# P08R7.net
KiCad netlist of a schematic drawn in EAGLE
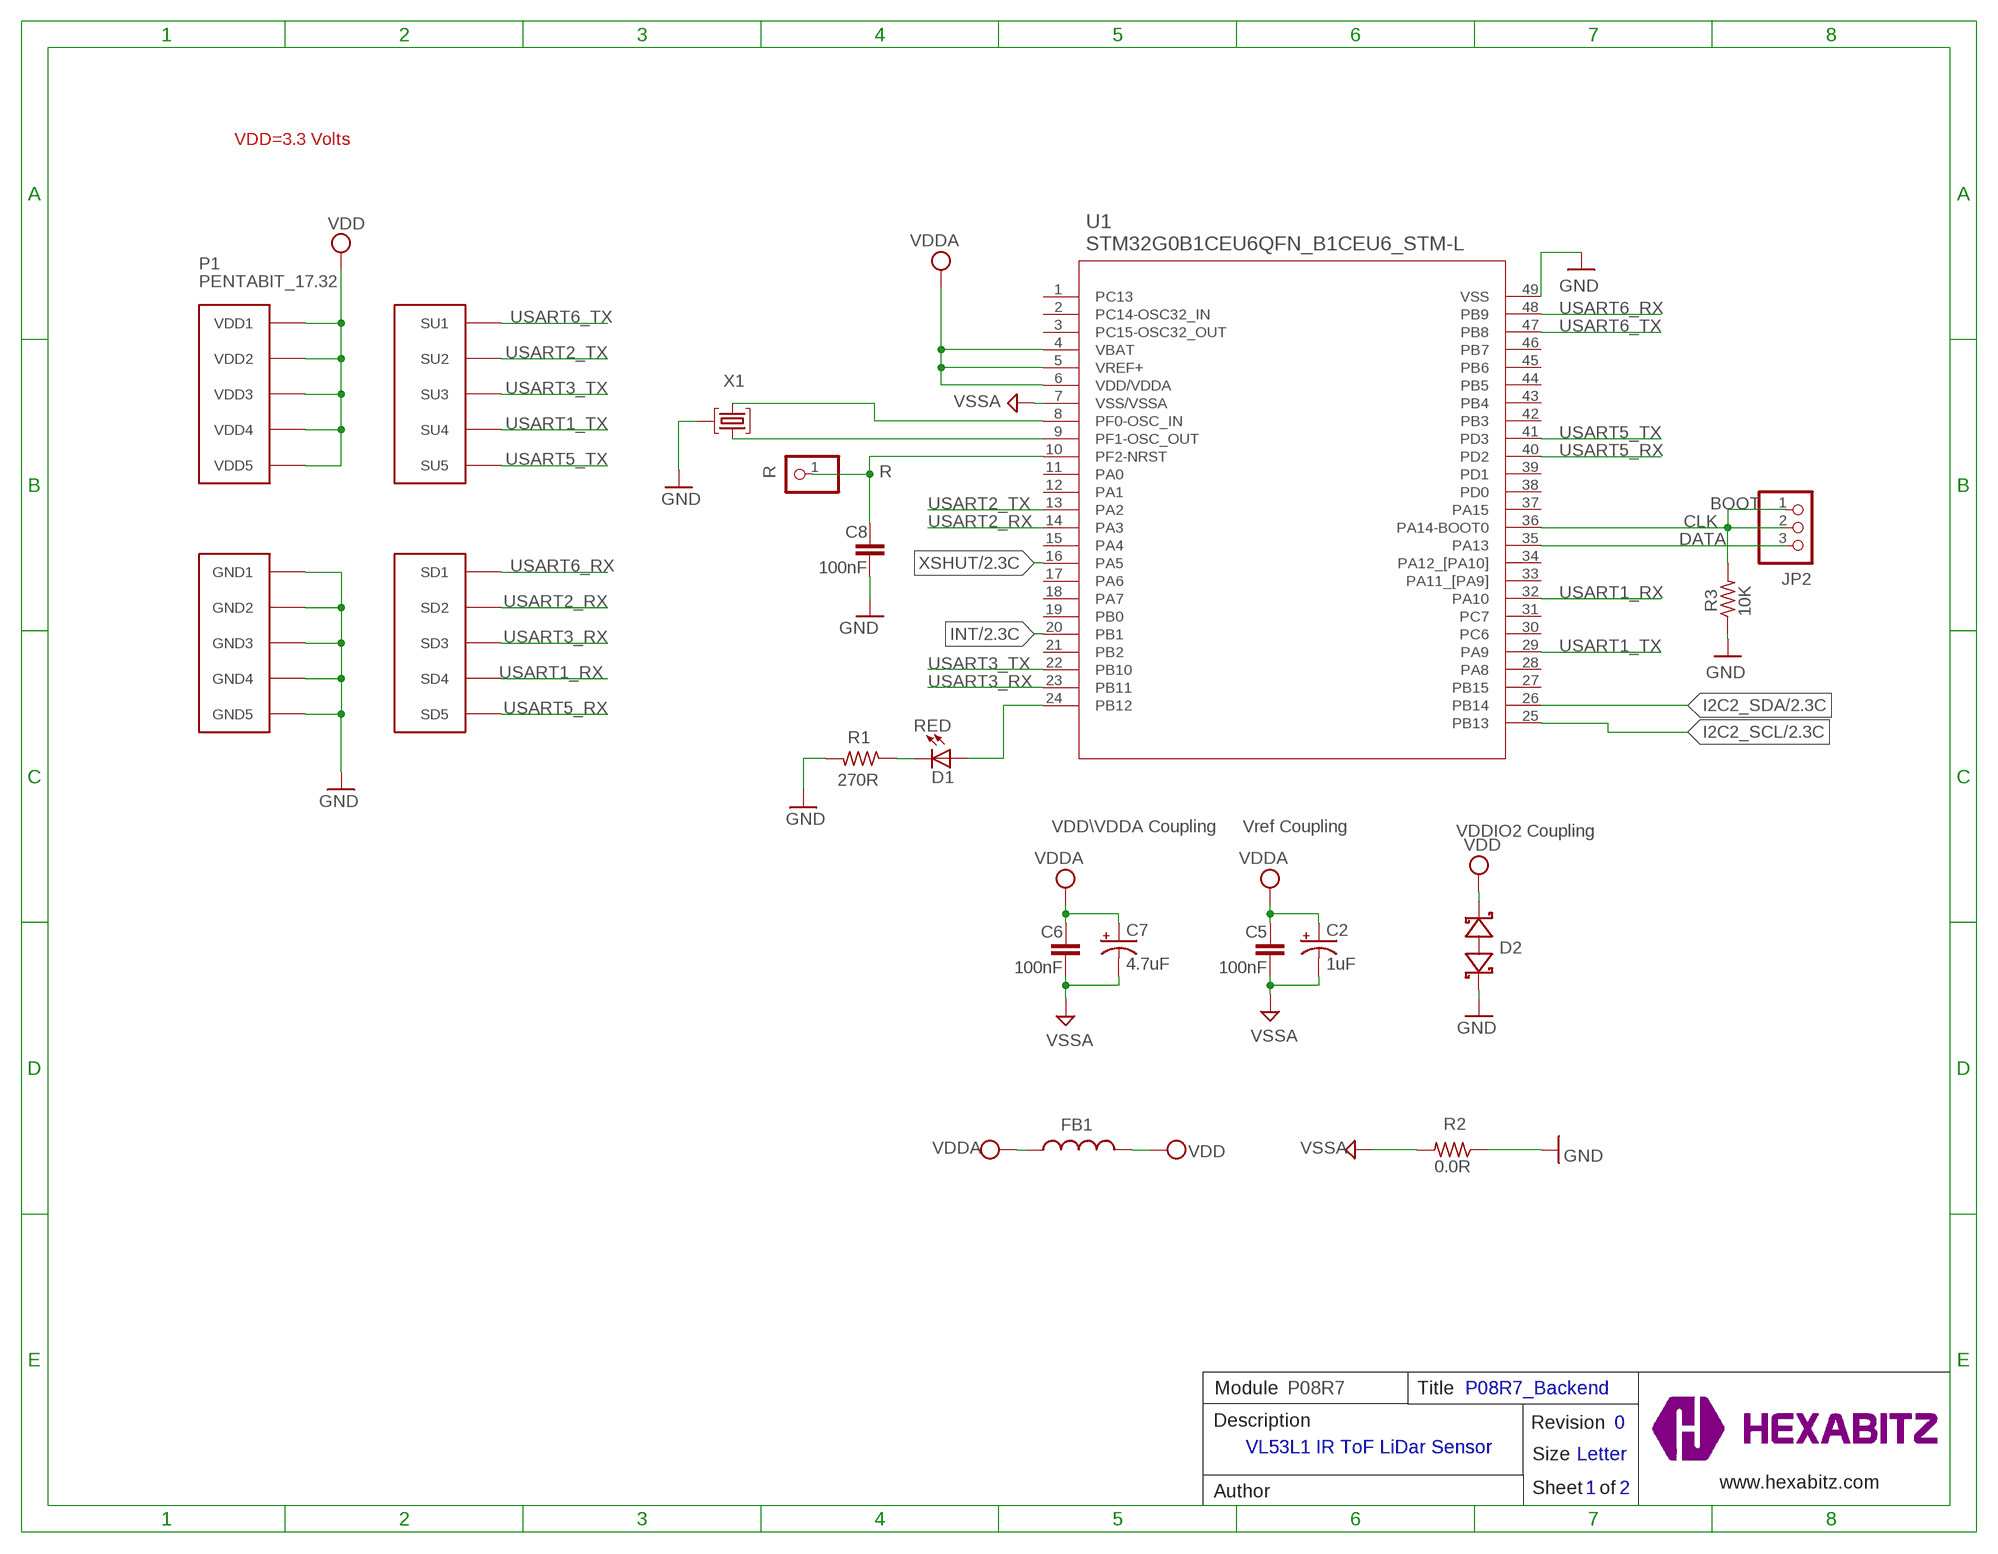
[diagram p0: schematic, sheet 1]
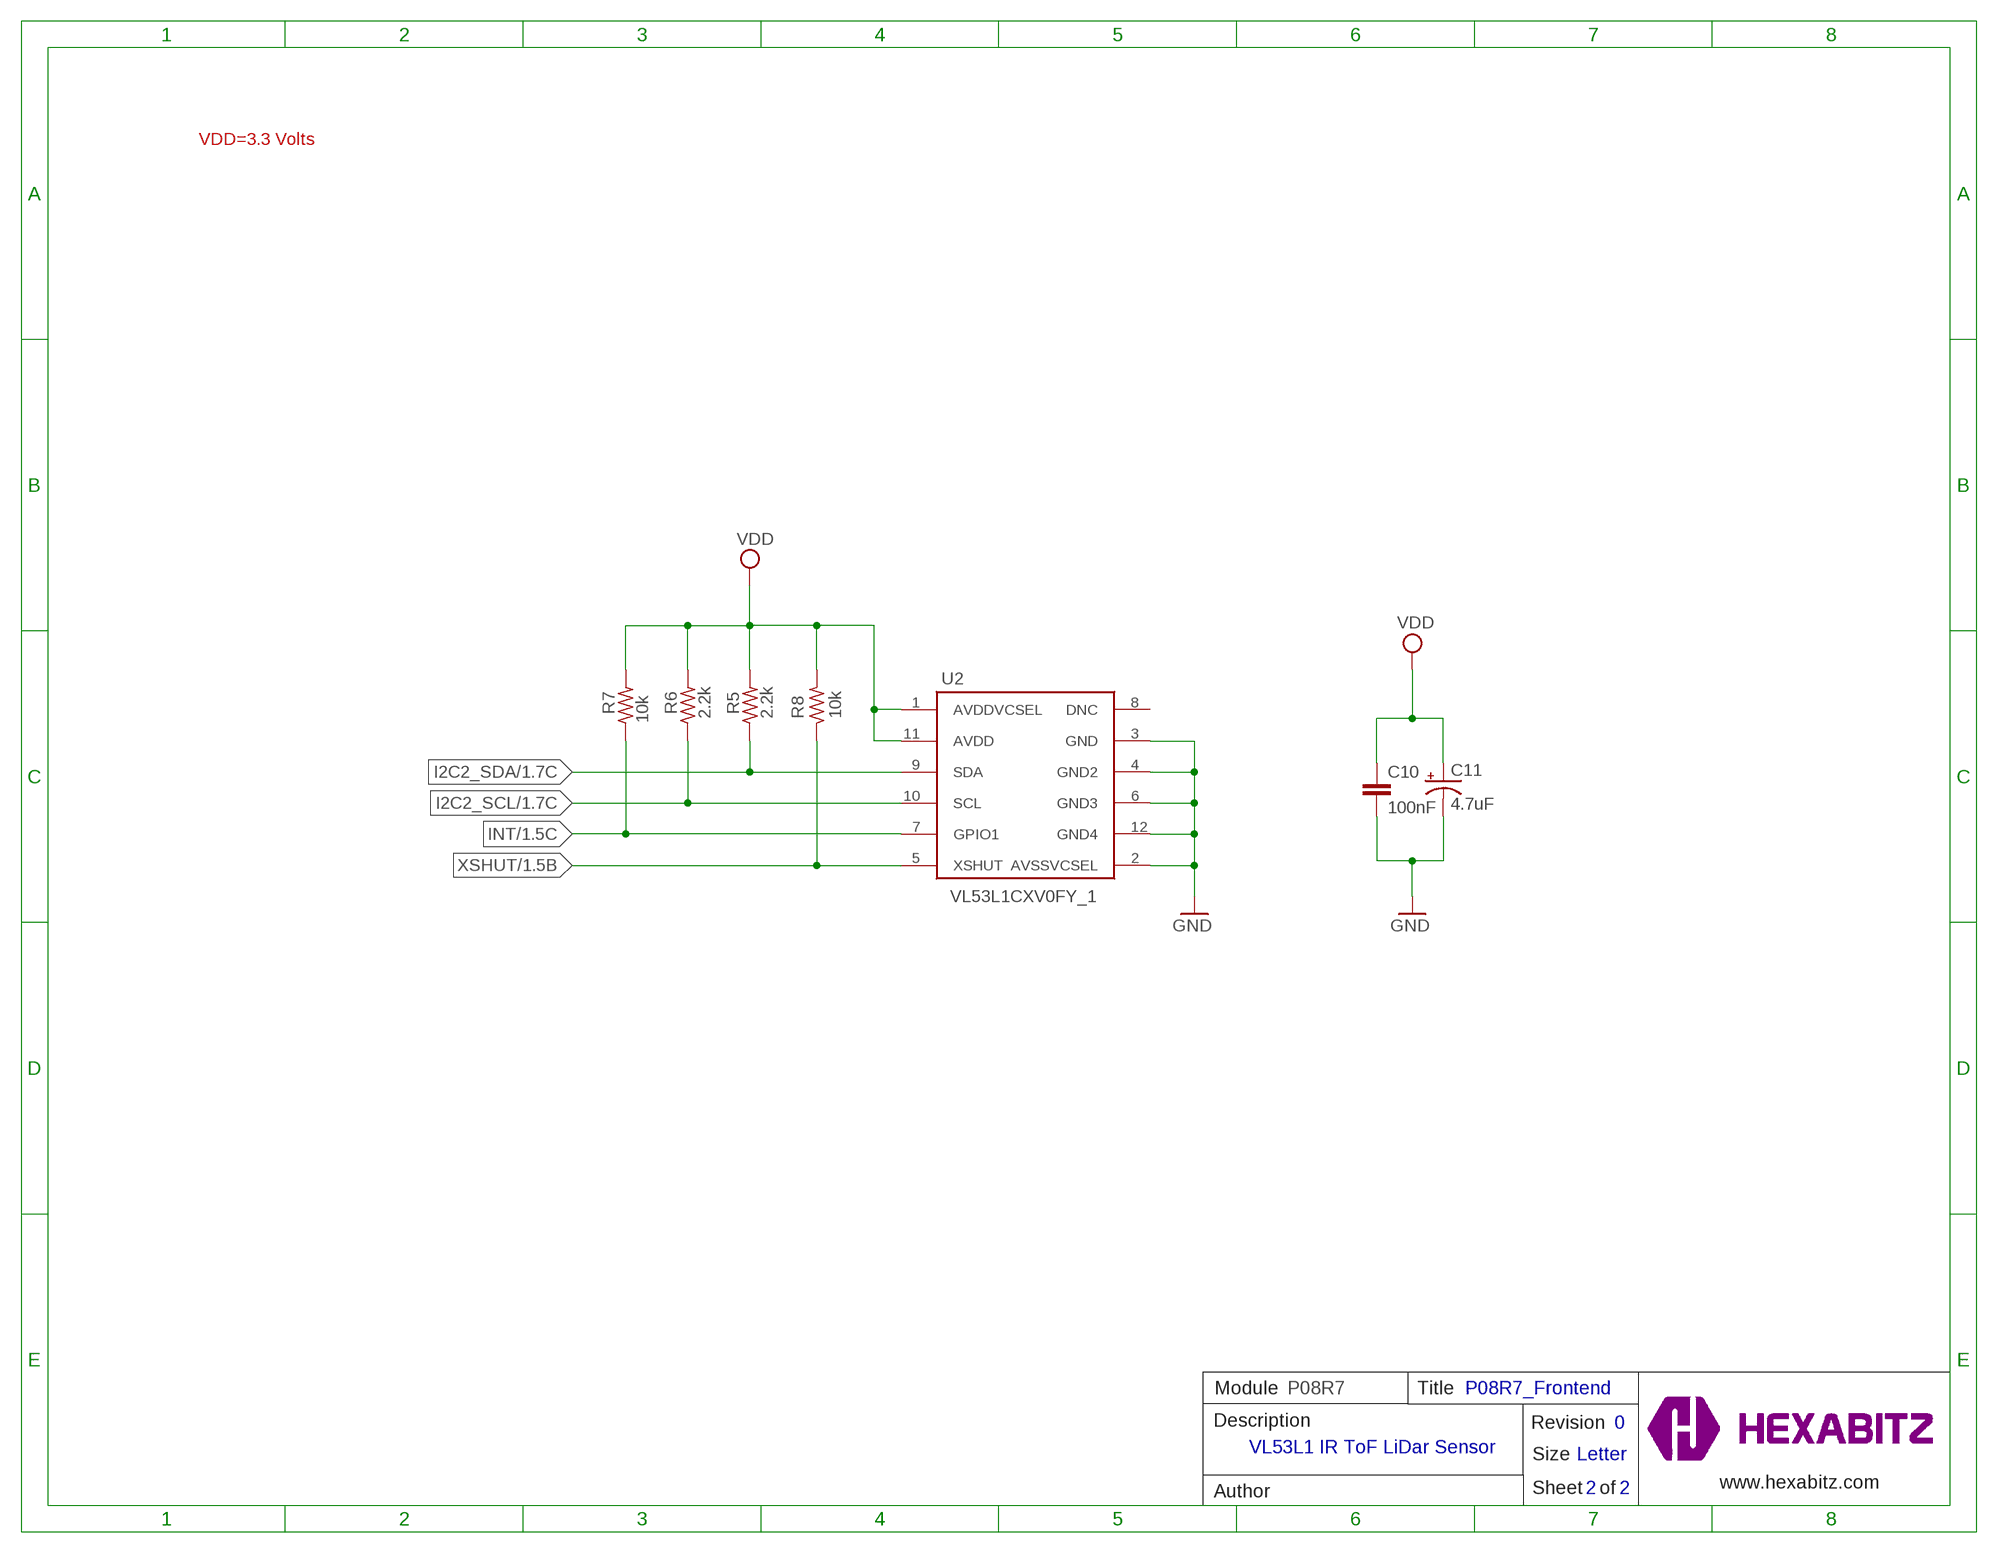
[diagram p1: schematic, sheet 2]

(export (version "E")
  (design (tool "Eeschema 10.0.6"))
  (components
    (comp (ref "C10")
      (value "100nF")
      (footprint "eagle-import:C-0603")
      (libsource (lib "eagle-import") (part "C-0603"))
    )
    (comp (ref "C11")
      (value "4.7uF")
      (footprint "eagle-import:C-0805-POL")
      (libsource (lib "eagle-import") (part "C-0805-POL"))
    )
    (comp (ref "R5")
      (value "2.2k")
      (footprint "eagle-import:R-0603")
      (libsource (lib "eagle-import") (part "R-0603"))
    )
    (comp (ref "R6")
      (value "2.2k")
      (footprint "eagle-import:R-0603")
      (libsource (lib "eagle-import") (part "R-0603"))
    )
    (comp (ref "R7")
      (value "10k")
      (footprint "eagle-import:R-0603")
      (libsource (lib "eagle-import") (part "R-0603"))
    )
    (comp (ref "R8")
      (value "10k")
      (footprint "eagle-import:R-0603")
      (libsource (lib "eagle-import") (part "R-0603"))
    )
    (comp (ref "U2")
      (value "VL53L1CXV0FY_1")
      (footprint "eagle-import:VL53L1CXV0FY1")
      (fields
        (field (name "MANUFACTURER_PART_NUMBER") "VL53L1CXV0FY/1")
        (field (name "MOUSER_PART_NUMBER") "511-VL53L1CXV0FY/1")
      )
      (libsource (lib "eagle-import") (part "VL53L1CXV0FY_1"))
    )
    (comp (ref "C2")
      (value "1uF")
      (footprint "eagle-import:C-0805-POL")
      (libsource (lib "eagle-import") (part "C-0805-POL"))
    )
    (comp (ref "C5")
      (value "100nF")
      (footprint "eagle-import:C-0603")
      (libsource (lib "eagle-import") (part "C-0603"))
    )
    (comp (ref "C6")
      (value "100nF")
      (footprint "eagle-import:C-0603")
      (libsource (lib "eagle-import") (part "C-0603"))
    )
    (comp (ref "C7")
      (value "4.7uF")
      (footprint "eagle-import:C-0805-POL")
      (libsource (lib "eagle-import") (part "C-0805-POL"))
    )
    (comp (ref "C8")
      (value "100nF")
      (footprint "eagle-import:C-0603")
      (libsource (lib "eagle-import") (part "C-0603"))
    )
    (comp (ref "D1")
      (value "RED")
      (footprint "eagle-import:VLMS1300-GS08")
      (fields
        (field (name "MPN") "VLMS1300-GS08")
        (field (name "MFN") "Vishay")
        (field (name "MPN_1") "VLMS1300-GS08")
        (field (name "OCTOPART_URL") "https://octopart.com/vlms1300-gs08-vishay-21709201?r=sp&s=_gcP4_q8T1SC6PJQPTQ9yA")
      )
      (libsource (lib "eagle-import") (part "VLMS1300-GS08"))
    )
    (comp (ref "D2")
      (value "BOURNS_CDSOD323-T03SCBOURNS_CDSOD323-T03SC_0_0")
      (footprint "eagle-import:BOURNS_CDSOD323-T03SC_0")
      (fields (field (name "MPN") "CDSOD323-T03SC"))
      (libsource (lib "eagle-import") (part "BOURNS_CDSOD323-T03SCBOURNS_CDSOD323-T03SC_0_0"))
    )
    (comp (ref "FB1")
      (value "FB-TDK_MMZ1608Y300B")
      (footprint "eagle-import:FB-TDK_MMZ1608Y300B")
      (fields
        (field (name "MFN") "TDK ")
        (field (name "MPN") "MMZ1608Y300B")
        (field (name "OCTOPART_URL") "https://octopart.com/mmz1608y300b-tdk-368280?r=sp&s=cd9_2ZEqQ9q9UNBuQgHAiA")
      )
      (libsource (lib "eagle-import") (part "FB-TDK_MMZ1608Y300B"))
    )
    (comp (ref "JP2")
      (value "PINHD-1X3")
      (footprint "eagle-import:1X03")
      (libsource (lib "eagle-import") (part "PINHD-1X3"))
    )
    (comp (ref "P1")
      (value "PENTABIT_17.32")
      (footprint "eagle-import:PENTABIT_17.32")
      (libsource (lib "eagle-import") (part "PENTABIT_?17.32"))
    )
    (comp (ref "R")
      (value "R")
      (footprint "eagle-import:1X01")
      (fields (field (name "MPN") "87227-1"))
      (libsource (lib "eagle-import") (part "PINHD-1X1"))
    )
    (comp (ref "R1")
      (value "270R")
      (footprint "eagle-import:R-0603")
      (libsource (lib "eagle-import") (part "R-0603"))
    )
    (comp (ref "R2")
      (value "0.0R")
      (footprint "eagle-import:R-0603")
      (fields
        (field (name "MFN") "Yageo")
        (field (name "MPN") "RC0603JR-070RL")
        (field (name "OCTOPART_URL") "https://octopart.com/rc0603jr-070rl-yageo-1241539?r=sp&s=X2NteqRjRNWrnx42Y0aliA")
        (field (name "RESISTANCE") "0.0 Ohm")
      )
      (libsource (lib "eagle-import") (part "R-0603"))
    )
    (comp (ref "R3")
      (value "10K")
      (footprint "eagle-import:R-0603")
      (libsource (lib "eagle-import") (part "R-0603"))
    )
    (comp (ref "TRIMBLE-LOGO1")
      (value "HEXA-LOGO")
      (footprint "eagle-import:HEXA-LOGO")
      (libsource (lib "eagle-import") (part "HEXA-LOGO"))
    )
    (comp (ref "U1")
      (value "STM32G0B1CEU6QFN_B1CEU6_STM-L")
      (footprint "eagle-import:QFN_B1CEU6_STM-L")
      (fields
        (field (name "MANUFACTURER_PART_NUMBER") "STM32G0B1CEU6")
        (field (name "COPYRIGHT") "Copyright (C) 2021 Ultra Librarian. All rights reserved.")
      )
      (libsource (lib "eagle-import") (part "STM32G0B1CEU6QFN_B1CEU6_STM-L"))
    )
    (comp (ref "X1")
      (value "XTALL_CSTCE8M00G52")
      (footprint "eagle-import:XTALL_CSTCE8M00G52")
      (fields (field (name "MPN") "CSTCE8M00G52Z-R0"))
      (libsource (lib "eagle-import") (part "XTALL_CSTCE8M00G52"))
    )
  )
  (nets
    (net (code "1") (name "CLK") (class "Default")
      (node (ref "JP2") (pin "1") (pinfunction "1_1") (pintype "passive"))
      (node (ref "JP2") (pin "2") (pinfunction "2_2") (pintype "passive"))
      (node (ref "R3") (pin "2") (pinfunction "2_2") (pintype "passive"))
      (node (ref "U1") (pin "36") (pinfunction "PA14-BOOT0_36") (pintype "bidirectional"))
    )
    (net (code "2") (name "DATA") (class "Default")
      (node (ref "JP2") (pin "3") (pinfunction "3_3") (pintype "passive"))
      (node (ref "U1") (pin "35") (pinfunction "PA13_35") (pintype "bidirectional"))
    )
    (net (code "3") (name "GND") (class "Default")
      (node (ref "C10") (pin "2") (pinfunction "2_2") (pintype "passive"))
      (node (ref "C11") (pin "2") (pinfunction "-_2") (pintype "passive"))
      (node (ref "C8") (pin "2") (pinfunction "2_2") (pintype "passive"))
      (node (ref "D2") (pin "1") (pinfunction "A_1") (pintype "passive"))
      (node (ref "P1") (pin "PAD_PD10") (pinfunction "GND5_PAD_PD10") (pintype "power_in"))
      (node (ref "P1") (pin "PAD_PD6") (pinfunction "GND1_PAD_PD6") (pintype "power_in"))
      (node (ref "P1") (pin "PAD_PD7") (pinfunction "GND2_PAD_PD7") (pintype "power_in"))
      (node (ref "P1") (pin "PAD_PD8") (pinfunction "GND3_PAD_PD8") (pintype "power_in"))
      (node (ref "P1") (pin "PAD_PD9") (pinfunction "GND4_PAD_PD9") (pintype "power_in"))
      (node (ref "R1") (pin "2") (pinfunction "2_2") (pintype "passive"))
      (node (ref "R2") (pin "1") (pinfunction "1_1") (pintype "passive"))
      (node (ref "R3") (pin "1") (pinfunction "1_1") (pintype "passive"))
      (node (ref "U1") (pin "49") (pinfunction "VSS_49") (pintype "passive"))
      (node (ref "U2") (pin "12") (pinfunction "GND4_12") (pintype "bidirectional"))
      (node (ref "U2") (pin "2") (pinfunction "AVSSVCSEL_2") (pintype "bidirectional"))
      (node (ref "U2") (pin "3") (pinfunction "GND_3") (pintype "bidirectional"))
      (node (ref "U2") (pin "4") (pinfunction "GND2_4") (pintype "bidirectional"))
      (node (ref "U2") (pin "6") (pinfunction "GND3_6") (pintype "bidirectional"))
      (node (ref "X1") (pin "P$2") (pinfunction "2_P$2") (pintype "passive"))
    )
    (net (code "4") (name "I2C2_SCL") (class "Default")
      (node (ref "R6") (pin "1") (pinfunction "1_1") (pintype "passive"))
      (node (ref "U1") (pin "25") (pinfunction "PB13_25") (pintype "bidirectional"))
      (node (ref "U2") (pin "10") (pinfunction "SCL_10") (pintype "bidirectional"))
    )
    (net (code "5") (name "I2C2_SDA") (class "Default")
      (node (ref "R5") (pin "1") (pinfunction "1_1") (pintype "passive"))
      (node (ref "U1") (pin "26") (pinfunction "PB14_26") (pintype "bidirectional"))
      (node (ref "U2") (pin "9") (pinfunction "SDA_9") (pintype "bidirectional"))
    )
    (net (code "6") (name "INT") (class "Default")
      (node (ref "R7") (pin "1") (pinfunction "1_1") (pintype "passive"))
      (node (ref "U1") (pin "20") (pinfunction "PB1_20") (pintype "bidirectional"))
      (node (ref "U2") (pin "7") (pinfunction "GPIO1_7") (pintype "bidirectional"))
    )
    (net (code "7") (name "Net-(D1-PadC)") (class "Default")
      (node (ref "D1") (pin "C") (pinfunction "C_C") (pintype "passive"))
      (node (ref "R1") (pin "1") (pinfunction "1_1") (pintype "passive"))
    )
    (net (code "8") (name "Net-(U1-PB12)") (class "Default")
      (node (ref "D1") (pin "A") (pinfunction "A_A") (pintype "passive"))
      (node (ref "U1") (pin "24") (pinfunction "PB12_24") (pintype "bidirectional"))
    )
    (net (code "9") (name "Net-(U1-PF0-OSC_IN)") (class "Default")
      (node (ref "U1") (pin "8") (pinfunction "PF0-OSC_IN_8") (pintype "bidirectional"))
      (node (ref "X1") (pin "P$3") (pinfunction "3_P$3") (pintype "passive"))
    )
    (net (code "10") (name "Net-(U1-PF1-OSC_OUT)") (class "Default")
      (node (ref "U1") (pin "9") (pinfunction "PF1-OSC_OUT_9") (pintype "output"))
      (node (ref "X1") (pin "P$1") (pinfunction "1_P$1") (pintype "passive"))
    )
    (net (code "11") (name "Net-(U1-PF2-NRST)") (class "Default")
      (node (ref "C8") (pin "1") (pinfunction "1_1") (pintype "passive"))
      (node (ref "R") (pin "1") (pinfunction "1_1") (pintype "passive"))
      (node (ref "U1") (pin "10") (pinfunction "PF2-NRST_10") (pintype "bidirectional"))
    )
    (net (code "12") (name "USART1_RX") (class "Default")
      (node (ref "P1") (pin "PAD_PD4") (pinfunction "SD4_PAD_PD4") (pintype "bidirectional"))
      (node (ref "U1") (pin "32") (pinfunction "PA10_32") (pintype "bidirectional"))
    )
    (net (code "13") (name "USART1_TX") (class "Default")
      (node (ref "P1") (pin "PAD_PU4") (pinfunction "SU4_PAD_PU4") (pintype "bidirectional"))
      (node (ref "U1") (pin "29") (pinfunction "PA9_29") (pintype "bidirectional"))
    )
    (net (code "14") (name "USART2_RX") (class "Default")
      (node (ref "P1") (pin "PAD_PD2") (pinfunction "SD2_PAD_PD2") (pintype "bidirectional"))
      (node (ref "U1") (pin "14") (pinfunction "PA3_14") (pintype "bidirectional"))
    )
    (net (code "15") (name "USART2_TX") (class "Default")
      (node (ref "P1") (pin "PAD_PU2") (pinfunction "SU2_PAD_PU2") (pintype "bidirectional"))
      (node (ref "U1") (pin "13") (pinfunction "PA2_13") (pintype "bidirectional"))
    )
    (net (code "16") (name "USART3_RX") (class "Default")
      (node (ref "P1") (pin "PAD_PD3") (pinfunction "SD3_PAD_PD3") (pintype "bidirectional"))
      (node (ref "U1") (pin "23") (pinfunction "PB11_23") (pintype "bidirectional"))
    )
    (net (code "17") (name "USART3_TX") (class "Default")
      (node (ref "P1") (pin "PAD_PU3") (pinfunction "SU3_PAD_PU3") (pintype "bidirectional"))
      (node (ref "U1") (pin "22") (pinfunction "PB10_22") (pintype "bidirectional"))
    )
    (net (code "18") (name "USART5_RX") (class "Default")
      (node (ref "P1") (pin "PAD_PD5") (pinfunction "SD5_PAD_PD5") (pintype "bidirectional"))
      (node (ref "U1") (pin "40") (pinfunction "PD2_40") (pintype "bidirectional"))
    )
    (net (code "19") (name "USART5_TX") (class "Default")
      (node (ref "P1") (pin "PAD_PU5") (pinfunction "SU5_PAD_PU5") (pintype "bidirectional"))
      (node (ref "U1") (pin "41") (pinfunction "PD3_41") (pintype "bidirectional"))
    )
    (net (code "20") (name "USART6_RX") (class "Default")
      (node (ref "P1") (pin "PAD_PD1") (pinfunction "SD1_PAD_PD1") (pintype "bidirectional"))
      (node (ref "U1") (pin "48") (pinfunction "PB9_48") (pintype "bidirectional"))
    )
    (net (code "21") (name "USART6_TX") (class "Default")
      (node (ref "P1") (pin "PAD_PU1") (pinfunction "SU1_PAD_PU1") (pintype "bidirectional"))
      (node (ref "U1") (pin "47") (pinfunction "PB8_47") (pintype "bidirectional"))
    )
    (net (code "22") (name "VDD") (class "Default")
      (node (ref "C10") (pin "1") (pinfunction "1_1") (pintype "passive"))
      (node (ref "C11") (pin "1") (pinfunction "+_1") (pintype "passive"))
      (node (ref "D2") (pin "2") (pinfunction "C_2") (pintype "passive"))
      (node (ref "FB1") (pin "2") (pinfunction "2_2") (pintype "passive"))
      (node (ref "P1") (pin "PAD_PU10") (pinfunction "VDD5_PAD_PU10") (pintype "power_in"))
      (node (ref "P1") (pin "PAD_PU6") (pinfunction "VDD1_PAD_PU6") (pintype "power_in"))
      (node (ref "P1") (pin "PAD_PU7") (pinfunction "VDD2_PAD_PU7") (pintype "power_in"))
      (node (ref "P1") (pin "PAD_PU8") (pinfunction "VDD3_PAD_PU8") (pintype "power_in"))
      (node (ref "P1") (pin "PAD_PU9") (pinfunction "VDD4_PAD_PU9") (pintype "power_in"))
      (node (ref "R5") (pin "2") (pinfunction "2_2") (pintype "passive"))
      (node (ref "R6") (pin "2") (pinfunction "2_2") (pintype "passive"))
      (node (ref "R7") (pin "2") (pinfunction "2_2") (pintype "passive"))
      (node (ref "R8") (pin "2") (pinfunction "2_2") (pintype "passive"))
      (node (ref "U2") (pin "1") (pinfunction "AVDDVCSEL_1") (pintype "bidirectional"))
      (node (ref "U2") (pin "11") (pinfunction "AVDD_11") (pintype "bidirectional"))
    )
    (net (code "23") (name "VDDA") (class "Default")
      (node (ref "C2") (pin "1") (pinfunction "+_1") (pintype "passive"))
      (node (ref "C5") (pin "1") (pinfunction "1_1") (pintype "passive"))
      (node (ref "C6") (pin "1") (pinfunction "1_1") (pintype "passive"))
      (node (ref "C7") (pin "1") (pinfunction "+_1") (pintype "passive"))
      (node (ref "FB1") (pin "1") (pinfunction "1_1") (pintype "passive"))
      (node (ref "U1") (pin "4") (pinfunction "VBAT_4") (pintype "passive"))
      (node (ref "U1") (pin "5") (pinfunction "VREF+_5") (pintype "power_in"))
      (node (ref "U1") (pin "6") (pinfunction "VDD/VDDA_6") (pintype "power_in"))
    )
    (net (code "24") (name "VSSA") (class "Default")
      (node (ref "C2") (pin "2") (pinfunction "-_2") (pintype "passive"))
      (node (ref "C5") (pin "2") (pinfunction "2_2") (pintype "passive"))
      (node (ref "C6") (pin "2") (pinfunction "2_2") (pintype "passive"))
      (node (ref "C7") (pin "2") (pinfunction "-_2") (pintype "passive"))
      (node (ref "R2") (pin "2") (pinfunction "2_2") (pintype "passive"))
      (node (ref "U1") (pin "7") (pinfunction "VSS/VSSA_7") (pintype "passive"))
    )
    (net (code "25") (name "XSHUT") (class "Default")
      (node (ref "R8") (pin "1") (pinfunction "1_1") (pintype "passive"))
      (node (ref "U1") (pin "16") (pinfunction "PA5_16") (pintype "bidirectional"))
      (node (ref "U2") (pin "5") (pinfunction "XSHUT_5") (pintype "bidirectional"))
    )
    (net (code "26") (name "unconnected-(U1-PA0-Pad11)") (class "Default")
      (node (ref "U1") (pin "11") (pinfunction "PA0_11") (pintype "bidirectional"))
    )
    (net (code "27") (name "unconnected-(U1-PA1-Pad12)") (class "Default")
      (node (ref "U1") (pin "12") (pinfunction "PA1_12") (pintype "bidirectional"))
    )
    (net (code "28") (name "unconnected-(U1-PA4-Pad15)") (class "Default")
      (node (ref "U1") (pin "15") (pinfunction "PA4_15") (pintype "bidirectional"))
    )
    (net (code "29") (name "unconnected-(U1-PA6-Pad17)") (class "Default")
      (node (ref "U1") (pin "17") (pinfunction "PA6_17") (pintype "bidirectional"))
    )
    (net (code "30") (name "unconnected-(U1-PA7-Pad18)") (class "Default")
      (node (ref "U1") (pin "18") (pinfunction "PA7_18") (pintype "bidirectional"))
    )
    (net (code "31") (name "unconnected-(U1-PA8-Pad28)") (class "Default")
      (node (ref "U1") (pin "28") (pinfunction "PA8_28") (pintype "bidirectional"))
    )
    (net (code "32") (name "unconnected-(U1-PA11_[PA9]-Pad33)") (class "Default")
      (node (ref "U1") (pin "33") (pinfunction "PA11_[PA9]_33") (pintype "bidirectional"))
    )
    (net (code "33") (name "unconnected-(U1-PA12_[PA10]-Pad34)") (class "Default")
      (node (ref "U1") (pin "34") (pinfunction "PA12_[PA10]_34") (pintype "bidirectional"))
    )
    (net (code "34") (name "unconnected-(U1-PA15-Pad37)") (class "Default")
      (node (ref "U1") (pin "37") (pinfunction "PA15_37") (pintype "bidirectional"))
    )
    (net (code "35") (name "unconnected-(U1-PB0-Pad19)") (class "Default")
      (node (ref "U1") (pin "19") (pinfunction "PB0_19") (pintype "bidirectional"))
    )
    (net (code "36") (name "unconnected-(U1-PB2-Pad21)") (class "Default")
      (node (ref "U1") (pin "21") (pinfunction "PB2_21") (pintype "bidirectional"))
    )
    (net (code "37") (name "unconnected-(U1-PB3-Pad42)") (class "Default")
      (node (ref "U1") (pin "42") (pinfunction "PB3_42") (pintype "bidirectional"))
    )
    (net (code "38") (name "unconnected-(U1-PB4-Pad43)") (class "Default")
      (node (ref "U1") (pin "43") (pinfunction "PB4_43") (pintype "bidirectional"))
    )
    (net (code "39") (name "unconnected-(U1-PB5-Pad44)") (class "Default")
      (node (ref "U1") (pin "44") (pinfunction "PB5_44") (pintype "bidirectional"))
    )
    (net (code "40") (name "unconnected-(U1-PB6-Pad45)") (class "Default")
      (node (ref "U1") (pin "45") (pinfunction "PB6_45") (pintype "bidirectional"))
    )
    (net (code "41") (name "unconnected-(U1-PB7-Pad46)") (class "Default")
      (node (ref "U1") (pin "46") (pinfunction "PB7_46") (pintype "bidirectional"))
    )
    (net (code "42") (name "unconnected-(U1-PB15-Pad27)") (class "Default")
      (node (ref "U1") (pin "27") (pinfunction "PB15_27") (pintype "bidirectional"))
    )
    (net (code "43") (name "unconnected-(U1-PC6-Pad30)") (class "Default")
      (node (ref "U1") (pin "30") (pinfunction "PC6_30") (pintype "bidirectional"))
    )
    (net (code "44") (name "unconnected-(U1-PC7-Pad31)") (class "Default")
      (node (ref "U1") (pin "31") (pinfunction "PC7_31") (pintype "bidirectional"))
    )
    (net (code "45") (name "unconnected-(U1-PC13-Pad1)") (class "Default")
      (node (ref "U1") (pin "1") (pinfunction "PC13_1") (pintype "bidirectional"))
    )
    (net (code "46") (name "unconnected-(U1-PC14-OSC32_IN-Pad2)") (class "Default")
      (node (ref "U1") (pin "2") (pinfunction "PC14-OSC32_IN_2") (pintype "bidirectional"))
    )
    (net (code "47") (name "unconnected-(U1-PC15-OSC32_OUT-Pad3)") (class "Default")
      (node (ref "U1") (pin "3") (pinfunction "PC15-OSC32_OUT_3") (pintype "output"))
    )
    (net (code "48") (name "unconnected-(U1-PD0-Pad38)") (class "Default")
      (node (ref "U1") (pin "38") (pinfunction "PD0_38") (pintype "bidirectional"))
    )
    (net (code "49") (name "unconnected-(U1-PD1-Pad39)") (class "Default")
      (node (ref "U1") (pin "39") (pinfunction "PD1_39") (pintype "bidirectional"))
    )
    (net (code "50") (name "unconnected-(U2-DNC-Pad8)") (class "Default")
      (node (ref "U2") (pin "8") (pinfunction "DNC_8") (pintype "no_connect"))
    )
  )
)
